# FPGA_MODULE.net
KiCad netlist of a schematic drawn in Altium Designer
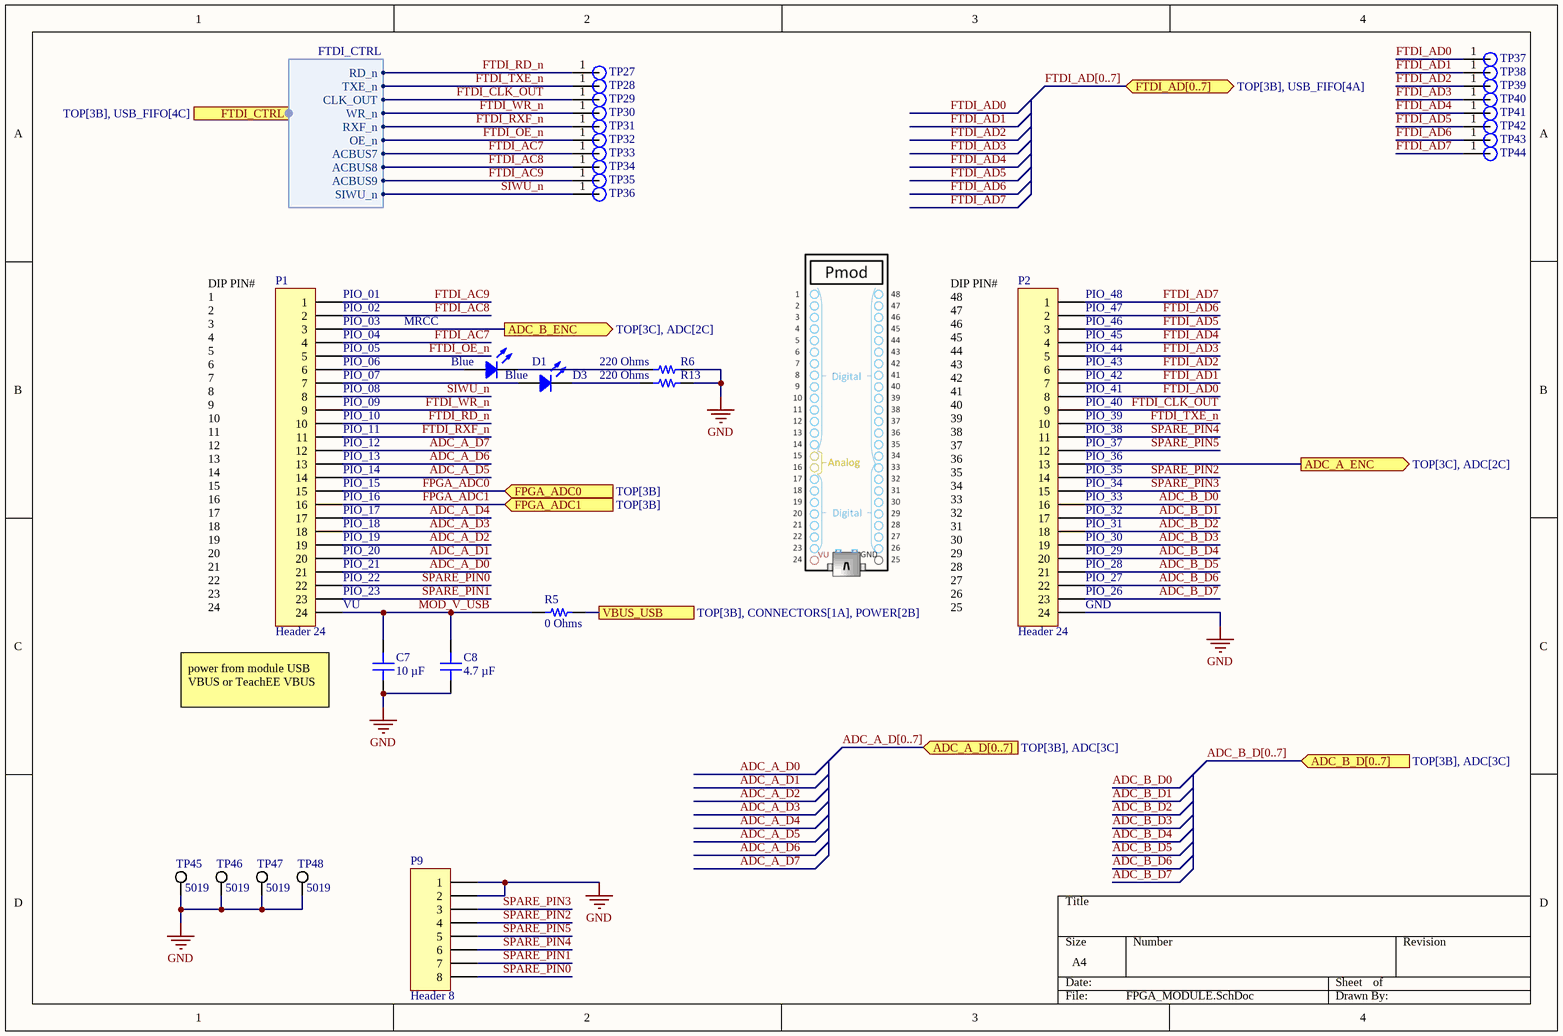
[diagram p0: FPGA_MODULE.SchDoc]

(export (version "E")
  (design (tool "Eeschema 10.0.6"))
  (components
    (comp (ref "C7")
      (value "10 µF")
      (footprint "CAP 0805_2012")
      (description "CAP CER 10UF 35V X6S 0805")
      (fields
        (field (name "PART NUMBER") "GRM21BC8YA106KE11L")
        (field (name "MANUFACTURER") "Murata Electronics")
      )
      (libsource (lib "Celestial") (part "Capacitor"))
    )
    (comp (ref "C8")
      (value "4.7 µF")
      (footprint "CAP 0402_1005")
      (description "CAP CER 4.7UF 16V X5R 0402")
      (fields
        (field (name "PART NUMBER") "CL05A475MO5NUNC")
        (field (name "MANUFACTURER") "Samsung Electro-Mechanics")
      )
      (libsource (lib "Celestial") (part "Capacitor"))
    )
    (comp (ref "D1")
      (value "Blue")
      (footprint "LED 1206_3216 BLUE")
      (description "LED SMD")
      (fields (field (name "PART NUMBER") "APTL3216QBC/D-01") (field (name "MANUFACTURER") "Kingbright"))
      (libsource (lib "Celestial") (part "LED"))
    )
    (comp (ref "D3")
      (value "Blue")
      (footprint "LED 1206_3216 BLUE")
      (description "LED SMD")
      (fields (field (name "PART NUMBER") "APTL3216QBC/D-01") (field (name "MANUFACTURER") "Kingbright"))
      (libsource (lib "Celestial") (part "LED"))
    )
    (comp (ref "P1")
      (value "Header 24")
      (footprint "HDR1X24")
      (description "Header, 24-Pin")
      (fields (field (name "PUBLISHER") "Altium Limited"))
      (libsource (lib "Miscellaneous Connectors") (part "Header 24"))
    )
    (comp (ref "P2")
      (value "Header 24")
      (footprint "HDR1X24")
      (description "Header, 24-Pin")
      (fields (field (name "PUBLISHER") "Altium Limited"))
      (libsource (lib "Miscellaneous Connectors") (part "Header 24"))
    )
    (comp (ref "P9")
      (value "Header 8")
      (footprint "HDR1X8")
      (description "Header, 8-Pin")
      (fields (field (name "PUBLISHER") "Altium Limited"))
      (libsource (lib "Miscellaneous Connectors") (part "Header 8"))
    )
    (comp (ref "R5")
      (value "0 Ohms")
      (footprint "RES 1206_3216")
      (description "1206 40 AMP JUMPER")
      (fields (field (name "PART NUMBER") "JR1206X40E") (field (name "MANUFACTURER") "Ohmite"))
      (libsource (lib "Celestial") (part "Resistor"))
    )
    (comp (ref "R6")
      (value "220 Ohms")
      (footprint "RES 0402_1005")
      (description "RES 220 OHM 1% 1/8W 0402")
      (fields
        (field (name "PART NUMBER") "CRGP0402F220R")
        (field (name "MANUFACTURER") "TE Connectivity Passive Product")
      )
      (libsource (lib "Celestial") (part "Resistor"))
    )
    (comp (ref "R13")
      (value "220 Ohms")
      (footprint "RES 0402_1005")
      (description "RES 220 OHM 1% 1/8W 0402")
      (fields
        (field (name "PART NUMBER") "CRGP0402F220R")
        (field (name "MANUFACTURER") "TE Connectivity Passive Product")
      )
      (libsource (lib "Celestial") (part "Resistor"))
    )
    (comp (ref "TP27") (value "Test Point") (footprint "ethan:TP1") (libsource (lib "ethan") (part "TP1")))
    (comp (ref "TP28") (value "Test Point") (footprint "ethan:TP1") (libsource (lib "ethan") (part "TP1")))
    (comp (ref "TP29") (value "Test Point") (footprint "ethan:TP1") (libsource (lib "ethan") (part "TP1")))
    (comp (ref "TP30") (value "Test Point") (footprint "ethan:TP1") (libsource (lib "ethan") (part "TP1")))
    (comp (ref "TP31") (value "Test Point") (footprint "ethan:TP1") (libsource (lib "ethan") (part "TP1")))
    (comp (ref "TP32") (value "Test Point") (footprint "ethan:TP1") (libsource (lib "ethan") (part "TP1")))
    (comp (ref "TP33") (value "Test Point") (footprint "ethan:TP1") (libsource (lib "ethan") (part "TP1")))
    (comp (ref "TP34") (value "Test Point") (footprint "ethan:TP1") (libsource (lib "ethan") (part "TP1")))
    (comp (ref "TP35") (value "Test Point") (footprint "ethan:TP1") (libsource (lib "ethan") (part "TP1")))
    (comp (ref "TP36") (value "Test Point") (footprint "ethan:TP1") (libsource (lib "ethan") (part "TP1")))
    (comp (ref "TP37") (value "Test Point") (footprint "ethan:TP1") (libsource (lib "ethan") (part "TP1")))
    (comp (ref "TP38") (value "Test Point") (footprint "ethan:TP1") (libsource (lib "ethan") (part "TP1")))
    (comp (ref "TP39") (value "Test Point") (footprint "ethan:TP1") (libsource (lib "ethan") (part "TP1")))
    (comp (ref "TP40") (value "Test Point") (footprint "ethan:TP1") (libsource (lib "ethan") (part "TP1")))
    (comp (ref "TP41") (value "Test Point") (footprint "ethan:TP1") (libsource (lib "ethan") (part "TP1")))
    (comp (ref "TP42") (value "Test Point") (footprint "ethan:TP1") (libsource (lib "ethan") (part "TP1")))
    (comp (ref "TP43") (value "Test Point") (footprint "ethan:TP1") (libsource (lib "ethan") (part "TP1")))
    (comp (ref "TP44") (value "Test Point") (footprint "ethan:TP1") (libsource (lib "ethan") (part "TP1")))
    (comp (ref "TP45")
      (value "5019")
      (footprint "KSTN-5019_V")
      (description "Test Point, 1 Position SMD, RoHS, Tape and Reel")
      (libsource (lib "Altium Content Vault") (part "TESTPOINT_WHITE"))
    )
    (comp (ref "TP46")
      (value "5019")
      (footprint "KSTN-5019_V")
      (description "Test Point, 1 Position SMD, RoHS, Tape and Reel")
      (libsource (lib "Altium Content Vault") (part "TESTPOINT_WHITE"))
    )
    (comp (ref "TP47")
      (value "5019")
      (footprint "KSTN-5019_V")
      (description "Test Point, 1 Position SMD, RoHS, Tape and Reel")
      (libsource (lib "Altium Content Vault") (part "TESTPOINT_WHITE"))
    )
    (comp (ref "TP48")
      (value "5019")
      (footprint "KSTN-5019_V")
      (description "Test Point, 1 Position SMD, RoHS, Tape and Reel")
      (libsource (lib "Altium Content Vault") (part "TESTPOINT_WHITE"))
    )
  )
  (nets
    (net (code "2") (name "/ADC_A_D0") (class "Default")
      (node (ref "P1") (pin "21") (pinfunction "21_21") (pintype "passive"))
    )
    (net (code "3") (name "/ADC_A_D1") (class "Default")
      (node (ref "P1") (pin "20") (pinfunction "20_20") (pintype "passive"))
    )
    (net (code "4") (name "/ADC_A_D2") (class "Default")
      (node (ref "P1") (pin "19") (pinfunction "19_19") (pintype "passive"))
    )
    (net (code "5") (name "/ADC_A_D3") (class "Default")
      (node (ref "P1") (pin "18") (pinfunction "18_18") (pintype "passive"))
    )
    (net (code "6") (name "/ADC_A_D4") (class "Default")
      (node (ref "P1") (pin "17") (pinfunction "17_17") (pintype "passive"))
    )
    (net (code "7") (name "/ADC_A_D5") (class "Default")
      (node (ref "P1") (pin "14") (pinfunction "14_14") (pintype "passive"))
    )
    (net (code "8") (name "/ADC_A_D6") (class "Default")
      (node (ref "P1") (pin "13") (pinfunction "13_13") (pintype "passive"))
    )
    (net (code "9") (name "/ADC_A_D7") (class "Default")
      (node (ref "P1") (pin "12") (pinfunction "12_12") (pintype "passive"))
    )
    (net (code "11") (name "/ADC_A_ENC") (class "Default")
      (node (ref "P2") (pin "13") (pinfunction "13_13") (pintype "passive"))
    )
    (net (code "12") (name "/ADC_B_D0") (class "Default")
      (node (ref "P2") (pin "16") (pinfunction "16_16") (pintype "passive"))
    )
    (net (code "13") (name "/ADC_B_D1") (class "Default")
      (node (ref "P2") (pin "17") (pinfunction "17_17") (pintype "passive"))
    )
    (net (code "14") (name "/ADC_B_D2") (class "Default")
      (node (ref "P2") (pin "18") (pinfunction "18_18") (pintype "passive"))
    )
    (net (code "15") (name "/ADC_B_D3") (class "Default")
      (node (ref "P2") (pin "19") (pinfunction "19_19") (pintype "passive"))
    )
    (net (code "16") (name "/ADC_B_D4") (class "Default")
      (node (ref "P2") (pin "20") (pinfunction "20_20") (pintype "passive"))
    )
    (net (code "17") (name "/ADC_B_D5") (class "Default")
      (node (ref "P2") (pin "21") (pinfunction "21_21") (pintype "passive"))
    )
    (net (code "18") (name "/ADC_B_D6") (class "Default")
      (node (ref "P2") (pin "22") (pinfunction "22_22") (pintype "passive"))
    )
    (net (code "19") (name "/ADC_B_D7") (class "Default")
      (node (ref "P2") (pin "23") (pinfunction "23_23") (pintype "passive"))
    )
    (net (code "21") (name "/ADC_B_ENC") (class "Default")
      (node (ref "P1") (pin "3") (pinfunction "3_3") (pintype "passive"))
    )
    (net (code "22") (name "/FPGA_ADC0") (class "Default")
      (node (ref "P1") (pin "15") (pinfunction "15_15") (pintype "passive"))
    )
    (net (code "23") (name "/FPGA_ADC1") (class "Default")
      (node (ref "P1") (pin "16") (pinfunction "16_16") (pintype "passive"))
    )
    (net (code "24") (name "/FTDI_AC7") (class "Default")
      (node (ref "P1") (pin "4") (pinfunction "4_4") (pintype "passive"))
      (node (ref "TP33") (pin "1") (pinfunction "1_1") (pintype "passive"))
    )
    (net (code "25") (name "/FTDI_AC8") (class "Default")
      (node (ref "P1") (pin "2") (pinfunction "2_2") (pintype "passive"))
      (node (ref "TP34") (pin "1") (pinfunction "1_1") (pintype "passive"))
    )
    (net (code "26") (name "/FTDI_AC9") (class "Default")
      (node (ref "P1") (pin "1") (pinfunction "1_1") (pintype "passive"))
      (node (ref "TP35") (pin "1") (pinfunction "1_1") (pintype "passive"))
    )
    (net (code "27") (name "/FTDI_AD0") (class "Default")
      (node (ref "P2") (pin "8") (pinfunction "8_8") (pintype "passive"))
      (node (ref "TP37") (pin "1") (pinfunction "1_1") (pintype "passive"))
    )
    (net (code "28") (name "/FTDI_AD1") (class "Default")
      (node (ref "P2") (pin "7") (pinfunction "7_7") (pintype "passive"))
      (node (ref "TP38") (pin "1") (pinfunction "1_1") (pintype "passive"))
    )
    (net (code "29") (name "/FTDI_AD2") (class "Default")
      (node (ref "P2") (pin "6") (pinfunction "6_6") (pintype "passive"))
      (node (ref "TP39") (pin "1") (pinfunction "1_1") (pintype "passive"))
    )
    (net (code "30") (name "/FTDI_AD3") (class "Default")
      (node (ref "P2") (pin "5") (pinfunction "5_5") (pintype "passive"))
      (node (ref "TP40") (pin "1") (pinfunction "1_1") (pintype "passive"))
    )
    (net (code "31") (name "/FTDI_AD4") (class "Default")
      (node (ref "P2") (pin "4") (pinfunction "4_4") (pintype "passive"))
      (node (ref "TP41") (pin "1") (pinfunction "1_1") (pintype "passive"))
    )
    (net (code "32") (name "/FTDI_AD5") (class "Default")
      (node (ref "P2") (pin "3") (pinfunction "3_3") (pintype "passive"))
      (node (ref "TP42") (pin "1") (pinfunction "1_1") (pintype "passive"))
    )
    (net (code "33") (name "/FTDI_AD6") (class "Default")
      (node (ref "P2") (pin "2") (pinfunction "2_2") (pintype "passive"))
      (node (ref "TP43") (pin "1") (pinfunction "1_1") (pintype "passive"))
    )
    (net (code "34") (name "/FTDI_AD7") (class "Default")
      (node (ref "P2") (pin "1") (pinfunction "1_1") (pintype "passive"))
      (node (ref "TP44") (pin "1") (pinfunction "1_1") (pintype "passive"))
    )
    (net (code "36") (name "/FTDI_CLK_OUT") (class "Default")
      (node (ref "P2") (pin "9") (pinfunction "9_9") (pintype "passive"))
      (node (ref "TP29") (pin "1") (pinfunction "1_1") (pintype "passive"))
    )
    (net (code "37") (name "/FTDI_OE_n") (class "Default")
      (node (ref "P1") (pin "5") (pinfunction "5_5") (pintype "passive"))
      (node (ref "TP32") (pin "1") (pinfunction "1_1") (pintype "passive"))
    )
    (net (code "38") (name "/FTDI_RD_n") (class "Default")
      (node (ref "P1") (pin "10") (pinfunction "10_10") (pintype "passive"))
      (node (ref "TP27") (pin "1") (pinfunction "1_1") (pintype "passive"))
    )
    (net (code "39") (name "/FTDI_RXF_n") (class "Default")
      (node (ref "P1") (pin "11") (pinfunction "11_11") (pintype "passive"))
      (node (ref "TP31") (pin "1") (pinfunction "1_1") (pintype "passive"))
    )
    (net (code "40") (name "/FTDI_TXE_n") (class "Default")
      (node (ref "P2") (pin "10") (pinfunction "10_10") (pintype "passive"))
      (node (ref "TP28") (pin "1") (pinfunction "1_1") (pintype "passive"))
    )
    (net (code "41") (name "/FTDI_WR_n") (class "Default")
      (node (ref "P1") (pin "9") (pinfunction "9_9") (pintype "passive"))
      (node (ref "TP30") (pin "1") (pinfunction "1_1") (pintype "passive"))
    )
    (net (code "42") (name "/MOD_V_USB") (class "Default")
      (node (ref "C7") (pin "2") (pinfunction "2_2") (pintype "passive"))
      (node (ref "C8") (pin "2") (pinfunction "2_2") (pintype "passive"))
      (node (ref "P1") (pin "24") (pinfunction "24_24") (pintype "passive"))
      (node (ref "R5") (pin "2") (pinfunction "2_2") (pintype "passive"))
    )
    (net (code "43") (name "/SIWU_n") (class "Default")
      (node (ref "P1") (pin "8") (pinfunction "8_8") (pintype "passive"))
      (node (ref "TP36") (pin "1") (pinfunction "1_1") (pintype "passive"))
    )
    (net (code "44") (name "/SPARE_PIN0") (class "Default")
      (node (ref "P1") (pin "22") (pinfunction "22_22") (pintype "passive"))
      (node (ref "P9") (pin "8") (pinfunction "8_8") (pintype "passive"))
    )
    (net (code "45") (name "/SPARE_PIN1") (class "Default")
      (node (ref "P1") (pin "23") (pinfunction "23_23") (pintype "passive"))
      (node (ref "P9") (pin "7") (pinfunction "7_7") (pintype "passive"))
    )
    (net (code "46") (name "/SPARE_PIN2") (class "Default")
      (node (ref "P2") (pin "14") (pinfunction "14_14") (pintype "passive"))
      (node (ref "P9") (pin "4") (pinfunction "4_4") (pintype "passive"))
    )
    (net (code "47") (name "/SPARE_PIN3") (class "Default")
      (node (ref "P2") (pin "15") (pinfunction "15_15") (pintype "passive"))
      (node (ref "P9") (pin "3") (pinfunction "3_3") (pintype "passive"))
    )
    (net (code "48") (name "/SPARE_PIN4") (class "Default")
      (node (ref "P2") (pin "11") (pinfunction "11_11") (pintype "passive"))
      (node (ref "P9") (pin "6") (pinfunction "6_6") (pintype "passive"))
    )
    (net (code "49") (name "/SPARE_PIN5") (class "Default")
      (node (ref "P2") (pin "12") (pinfunction "12_12") (pintype "passive"))
      (node (ref "P9") (pin "5") (pinfunction "5_5") (pintype "passive"))
    )
    (net (code "50") (name "/VBUS_USB") (class "Default")
      (node (ref "R5") (pin "1") (pinfunction "1_1") (pintype "passive"))
    )
    (net (code "52") (name "GND") (class "Default")
      (node (ref "C7") (pin "1") (pinfunction "1_1") (pintype "passive"))
      (node (ref "C8") (pin "1") (pinfunction "1_1") (pintype "passive"))
      (node (ref "P2") (pin "24") (pinfunction "24_24") (pintype "passive"))
      (node (ref "P9") (pin "1") (pinfunction "1_1") (pintype "passive"))
      (node (ref "P9") (pin "2") (pinfunction "2_2") (pintype "passive"))
      (node (ref "R13") (pin "1") (pinfunction "1_1") (pintype "passive"))
      (node (ref "R6") (pin "1") (pinfunction "1_1") (pintype "passive"))
      (node (ref "TP45") (pin "1") (pinfunction "1_1") (pintype "passive"))
      (node (ref "TP46") (pin "1") (pinfunction "1_1") (pintype "passive"))
      (node (ref "TP47") (pin "1") (pinfunction "1_1") (pintype "passive"))
      (node (ref "TP48") (pin "1") (pinfunction "1_1") (pintype "passive"))
    )
    (net (code "53") (name "Net-(D1-Pad1)") (class "Default")
      (node (ref "D1") (pin "1") (pinfunction "1_1") (pintype "passive"))
      (node (ref "P1") (pin "6") (pinfunction "6_6") (pintype "passive"))
    )
    (net (code "54") (name "Net-(D1-Pad2)") (class "Default")
      (node (ref "D1") (pin "2") (pinfunction "2_2") (pintype "passive"))
      (node (ref "R6") (pin "2") (pinfunction "2_2") (pintype "passive"))
    )
    (net (code "55") (name "Net-(D3-Pad1)") (class "Default")
      (node (ref "D3") (pin "1") (pinfunction "1_1") (pintype "passive"))
      (node (ref "P1") (pin "7") (pinfunction "7_7") (pintype "passive"))
    )
    (net (code "56") (name "Net-(D3-Pad2)") (class "Default")
      (node (ref "D3") (pin "2") (pinfunction "2_2") (pintype "passive"))
      (node (ref "R13") (pin "2") (pinfunction "2_2") (pintype "passive"))
    )
  )
)
